# PowerPCB.net
KiCad netlist of a schematic drawn in EAGLE
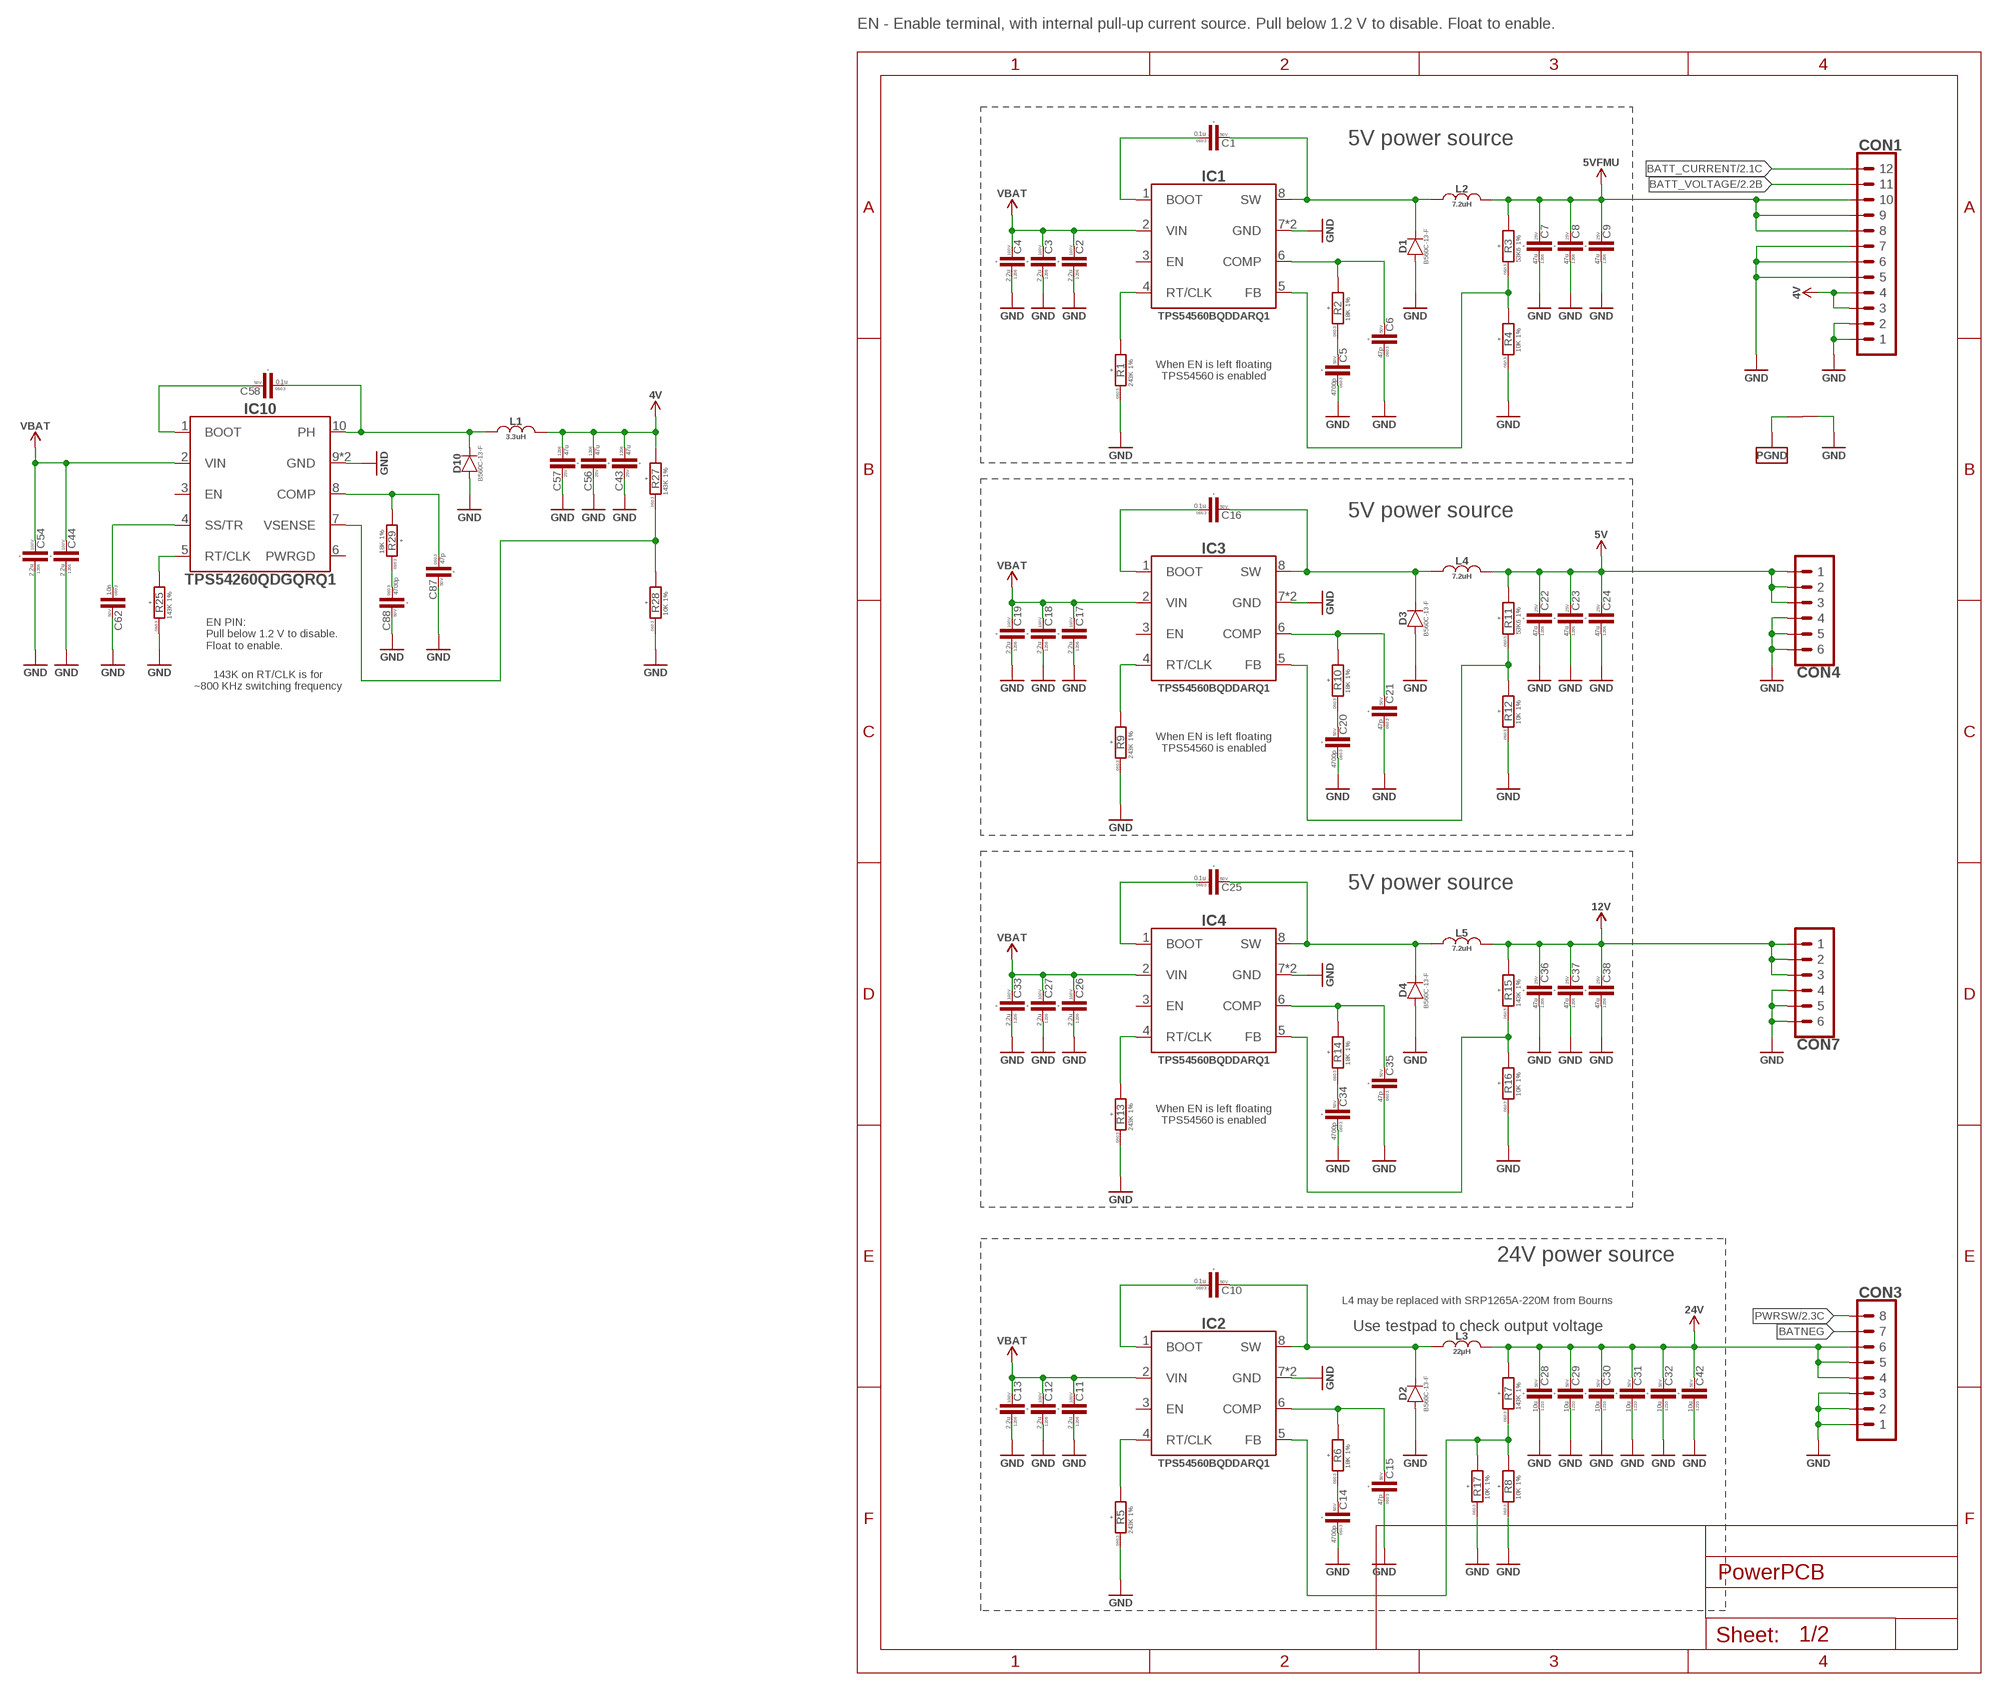
[diagram p0: schematic, sheet 1]
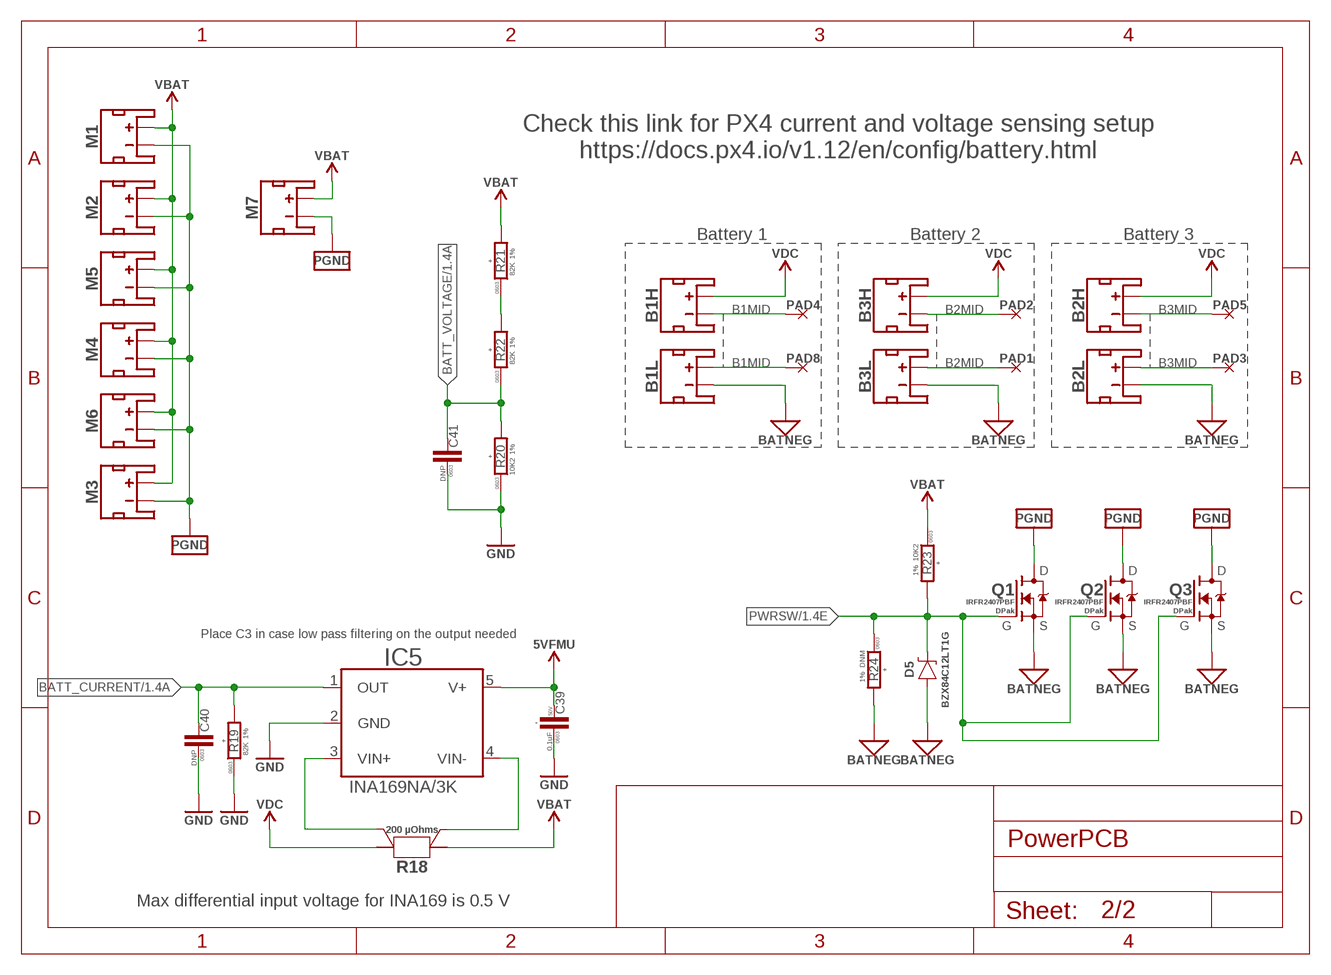
[diagram p1: schematic, sheet 2]

(export (version "E")
  (design (tool "Eeschema 10.0.6"))
  (components
    (comp (ref "C1")
      (value "0.1u")
      (footprint "eagle-import:C0603")
      (fields
        (field (name "PACKAGE") "0603")
        (field (name "ALLOCATED") "+")
        (field (name "LCSC#") "C14663")
        (field (name "MANF") "YAGEO")
        (field (name "MANF#") "CC0603KRX7R9BB104")
        (field (name "VOLTAGE") "50V")
      )
      (libsource (lib "eagle-import") (part "C-0603"))
    )
    (comp (ref "C2")
      (value "2.2u")
      (footprint "eagle-import:C1206")
      (fields
        (field (name "PACKAGE") "1206")
        (field (name "ALLOCATED") "+")
        (field (name "LCSC#") "C170101")
        (field (name "MANF") "Samsung Electro-Mechanics")
        (field (name "MANF#") "CL31B225KCHSNNE")
        (field (name "VOLTAGE") "100V")
      )
      (libsource (lib "eagle-import") (part "C-1206"))
    )
    (comp (ref "C3")
      (value "2.2u")
      (footprint "eagle-import:C1206")
      (fields
        (field (name "PACKAGE") "1206")
        (field (name "ALLOCATED") "+")
        (field (name "LCSC#") "C170101")
        (field (name "MANF") "Samsung Electro-Mechanics")
        (field (name "MANF#") "CL31B225KCHSNNE")
        (field (name "VOLTAGE") "100V")
      )
      (libsource (lib "eagle-import") (part "C-1206"))
    )
    (comp (ref "C4")
      (value "2.2u")
      (footprint "eagle-import:C1206")
      (fields
        (field (name "PACKAGE") "1206")
        (field (name "ALLOCATED") "+")
        (field (name "LCSC#") "C170101")
        (field (name "MANF") "Samsung Electro-Mechanics")
        (field (name "MANF#") "CL31B225KCHSNNE")
        (field (name "VOLTAGE") "100V")
      )
      (libsource (lib "eagle-import") (part "C-1206"))
    )
    (comp (ref "C5")
      (value "4700p")
      (footprint "eagle-import:C0603")
      (fields
        (field (name "PACKAGE") "0603")
        (field (name "ALLOCATED") "+")
        (field (name "LCSC#") "C106218")
        (field (name "MANF") "YAGEO")
        (field (name "MANF#") "CC0603KRX7R9BB472")
        (field (name "VOLTAGE") "50V")
      )
      (libsource (lib "eagle-import") (part "C-0603"))
    )
    (comp (ref "C6")
      (value "47p")
      (footprint "eagle-import:C0603")
      (fields
        (field (name "PACKAGE") "0603")
        (field (name "ALLOCATED") "+")
        (field (name "LCSC#") "C1671")
        (field (name "MANF") "Samsung Electro-Mechanics")
        (field (name "MANF#") "CL10C470JB8NNNC")
        (field (name "VOLTAGE") "50V")
      )
      (libsource (lib "eagle-import") (part "C-0603"))
    )
    (comp (ref "C7")
      (value "47u")
      (footprint "eagle-import:C1206")
      (fields
        (field (name "PACKAGE") "1206")
        (field (name "ALLOCATED") "+")
        (field (name "LCSC#") "C403725")
        (field (name "MANF") "Murata Electronics")
        (field (name "MANF#") "GRM31CR61E476ME44L")
        (field (name "VOLTAGE") "25V")
      )
      (libsource (lib "eagle-import") (part "C-1206"))
    )
    (comp (ref "C8")
      (value "47u")
      (footprint "eagle-import:C1206")
      (fields
        (field (name "PACKAGE") "1206")
        (field (name "ALLOCATED") "+")
        (field (name "LCSC#") "C403725")
        (field (name "MANF") "Murata Electronics")
        (field (name "MANF#") "GRM31CR61E476ME44L")
        (field (name "VOLTAGE") "25V")
      )
      (libsource (lib "eagle-import") (part "C-1206"))
    )
    (comp (ref "C9")
      (value "47u")
      (footprint "eagle-import:C1206")
      (fields
        (field (name "PACKAGE") "1206")
        (field (name "ALLOCATED") "+")
        (field (name "LCSC#") "C403725")
        (field (name "MANF") "Murata Electronics")
        (field (name "MANF#") "GRM31CR61E476ME44L")
        (field (name "VOLTAGE") "25V")
      )
      (libsource (lib "eagle-import") (part "C-1206"))
    )
    (comp (ref "C10")
      (value "0.1u")
      (footprint "eagle-import:C0603")
      (fields
        (field (name "PACKAGE") "0603")
        (field (name "ALLOCATED") "+")
        (field (name "LCSC#") "C14663")
        (field (name "MANF") "YAGEO")
        (field (name "MANF#") "CC0603KRX7R9BB104")
        (field (name "VOLTAGE") "50V")
      )
      (libsource (lib "eagle-import") (part "C-0603"))
    )
    (comp (ref "C11")
      (value "2.2u")
      (footprint "eagle-import:C1206")
      (fields
        (field (name "PACKAGE") "1206")
        (field (name "ALLOCATED") "+")
        (field (name "LCSC#") "C170101")
        (field (name "MANF") "Samsung Electro-Mechanics")
        (field (name "MANF#") "CL31B225KCHSNNE")
        (field (name "VOLTAGE") "100V")
      )
      (libsource (lib "eagle-import") (part "C-1206"))
    )
    (comp (ref "C12")
      (value "2.2u")
      (footprint "eagle-import:C1206")
      (fields
        (field (name "PACKAGE") "1206")
        (field (name "ALLOCATED") "+")
        (field (name "LCSC#") "C170101")
        (field (name "MANF") "Samsung Electro-Mechanics")
        (field (name "MANF#") "CL31B225KCHSNNE")
        (field (name "VOLTAGE") "100V")
      )
      (libsource (lib "eagle-import") (part "C-1206"))
    )
    (comp (ref "C13")
      (value "2.2u")
      (footprint "eagle-import:C1206")
      (fields
        (field (name "PACKAGE") "1206")
        (field (name "ALLOCATED") "+")
        (field (name "LCSC#") "C170101")
        (field (name "MANF") "Samsung Electro-Mechanics")
        (field (name "MANF#") "CL31B225KCHSNNE")
        (field (name "VOLTAGE") "100V")
      )
      (libsource (lib "eagle-import") (part "C-1206"))
    )
    (comp (ref "C14")
      (value "4700p")
      (footprint "eagle-import:C0603")
      (fields
        (field (name "PACKAGE") "0603")
        (field (name "ALLOCATED") "+")
        (field (name "LCSC#") "C106218")
        (field (name "MANF") "YAGEO")
        (field (name "MANF#") "CC0603KRX7R9BB472")
        (field (name "VOLTAGE") "50V")
      )
      (libsource (lib "eagle-import") (part "C-0603"))
    )
    (comp (ref "C15")
      (value "47p")
      (footprint "eagle-import:C0603")
      (fields
        (field (name "PACKAGE") "0603")
        (field (name "ALLOCATED") "+")
        (field (name "LCSC#") "C1671")
        (field (name "MANF") "Samsung Electro-Mechanics")
        (field (name "MANF#") "CL10C470JB8NNNC")
        (field (name "VOLTAGE") "50V")
      )
      (libsource (lib "eagle-import") (part "C-0603"))
    )
    (comp (ref "C16")
      (value "0.1u")
      (footprint "eagle-import:C0603")
      (fields
        (field (name "PACKAGE") "0603")
        (field (name "ALLOCATED") "+")
        (field (name "LCSC#") "C14663")
        (field (name "MANF") "YAGEO")
        (field (name "MANF#") "CC0603KRX7R9BB104")
        (field (name "VOLTAGE") "50V")
      )
      (libsource (lib "eagle-import") (part "C-0603"))
    )
    (comp (ref "C17")
      (value "2.2u")
      (footprint "eagle-import:C1206")
      (fields
        (field (name "PACKAGE") "1206")
        (field (name "ALLOCATED") "+")
        (field (name "LCSC#") "C170101")
        (field (name "MANF") "Samsung Electro-Mechanics")
        (field (name "MANF#") "CL31B225KCHSNNE")
        (field (name "VOLTAGE") "100V")
      )
      (libsource (lib "eagle-import") (part "C-1206"))
    )
    (comp (ref "C18")
      (value "2.2u")
      (footprint "eagle-import:C1206")
      (fields
        (field (name "PACKAGE") "1206")
        (field (name "ALLOCATED") "+")
        (field (name "LCSC#") "C170101")
        (field (name "MANF") "Samsung Electro-Mechanics")
        (field (name "MANF#") "CL31B225KCHSNNE")
        (field (name "VOLTAGE") "100V")
      )
      (libsource (lib "eagle-import") (part "C-1206"))
    )
    (comp (ref "C19")
      (value "2.2u")
      (footprint "eagle-import:C1206")
      (fields
        (field (name "PACKAGE") "1206")
        (field (name "ALLOCATED") "+")
        (field (name "LCSC#") "C170101")
        (field (name "MANF") "Samsung Electro-Mechanics")
        (field (name "MANF#") "CL31B225KCHSNNE")
        (field (name "VOLTAGE") "100V")
      )
      (libsource (lib "eagle-import") (part "C-1206"))
    )
    (comp (ref "C20")
      (value "4700p")
      (footprint "eagle-import:C0603")
      (fields
        (field (name "PACKAGE") "0603")
        (field (name "ALLOCATED") "+")
        (field (name "LCSC#") "C106218")
        (field (name "MANF") "YAGEO")
        (field (name "MANF#") "CC0603KRX7R9BB472")
        (field (name "VOLTAGE") "50V")
      )
      (libsource (lib "eagle-import") (part "C-0603"))
    )
    (comp (ref "C21")
      (value "47p")
      (footprint "eagle-import:C0603")
      (fields
        (field (name "PACKAGE") "0603")
        (field (name "ALLOCATED") "+")
        (field (name "LCSC#") "C1671")
        (field (name "MANF") "Samsung Electro-Mechanics")
        (field (name "MANF#") "CL10C470JB8NNNC")
        (field (name "VOLTAGE") "50V")
      )
      (libsource (lib "eagle-import") (part "C-0603"))
    )
    (comp (ref "C22")
      (value "47u")
      (footprint "eagle-import:C1206")
      (fields
        (field (name "PACKAGE") "1206")
        (field (name "ALLOCATED") "+")
        (field (name "LCSC#") "C403725")
        (field (name "MANF") "Murata Electronics")
        (field (name "MANF#") "GRM31CR61E476ME44L")
        (field (name "VOLTAGE") "25V")
      )
      (libsource (lib "eagle-import") (part "C-1206"))
    )
    (comp (ref "C23")
      (value "47u")
      (footprint "eagle-import:C1206")
      (fields
        (field (name "PACKAGE") "1206")
        (field (name "ALLOCATED") "+")
        (field (name "LCSC#") "C403725")
        (field (name "MANF") "Murata Electronics")
        (field (name "MANF#") "GRM31CR61E476ME44L")
        (field (name "VOLTAGE") "25V")
      )
      (libsource (lib "eagle-import") (part "C-1206"))
    )
    (comp (ref "C24")
      (value "47u")
      (footprint "eagle-import:C1206")
      (fields
        (field (name "PACKAGE") "1206")
        (field (name "ALLOCATED") "+")
        (field (name "LCSC#") "C403725")
        (field (name "MANF") "Murata Electronics")
        (field (name "MANF#") "GRM31CR61E476ME44L")
        (field (name "VOLTAGE") "25V")
      )
      (libsource (lib "eagle-import") (part "C-1206"))
    )
    (comp (ref "C25")
      (value "0.1u")
      (footprint "eagle-import:C0603")
      (fields
        (field (name "PACKAGE") "0603")
        (field (name "ALLOCATED") "+")
        (field (name "LCSC#") "C14663")
        (field (name "MANF") "YAGEO")
        (field (name "MANF#") "CC0603KRX7R9BB104")
        (field (name "VOLTAGE") "50V")
      )
      (libsource (lib "eagle-import") (part "C-0603"))
    )
    (comp (ref "C26")
      (value "2.2u")
      (footprint "eagle-import:C1206")
      (fields
        (field (name "PACKAGE") "1206")
        (field (name "ALLOCATED") "+")
        (field (name "LCSC#") "C170101")
        (field (name "MANF") "Samsung Electro-Mechanics")
        (field (name "MANF#") "CL31B225KCHSNNE")
        (field (name "VOLTAGE") "100V")
      )
      (libsource (lib "eagle-import") (part "C-1206"))
    )
    (comp (ref "C27")
      (value "2.2u")
      (footprint "eagle-import:C1206")
      (fields
        (field (name "PACKAGE") "1206")
        (field (name "ALLOCATED") "+")
        (field (name "LCSC#") "C170101")
        (field (name "MANF") "Samsung Electro-Mechanics")
        (field (name "MANF#") "CL31B225KCHSNNE")
        (field (name "VOLTAGE") "100V")
      )
      (libsource (lib "eagle-import") (part "C-1206"))
    )
    (comp (ref "C28")
      (value "10u")
      (footprint "eagle-import:C1210")
      (fields
        (field (name "PACKAGE") "1210")
        (field (name "ALLOCATED") "+")
        (field (name "LCSC#") "C77102")
        (field (name "MANF") "Murata Electronics")
        (field (name "MANF#") "GRM32ER71H106K")
        (field (name "VOLTAGE") "50V")
      )
      (libsource (lib "eagle-import") (part "C-1210"))
    )
    (comp (ref "C29")
      (value "10u")
      (footprint "eagle-import:C1210")
      (fields
        (field (name "PACKAGE") "1210")
        (field (name "ALLOCATED") "+")
        (field (name "LCSC#") "C77102")
        (field (name "MANF") "Murata Electronics")
        (field (name "MANF#") "GRM32ER71H106K")
        (field (name "VOLTAGE") "50V")
      )
      (libsource (lib "eagle-import") (part "C-1210"))
    )
    (comp (ref "C30")
      (value "10u")
      (footprint "eagle-import:C1210")
      (fields
        (field (name "PACKAGE") "1210")
        (field (name "ALLOCATED") "+")
        (field (name "LCSC#") "C77102")
        (field (name "MANF") "Murata Electronics")
        (field (name "MANF#") "GRM32ER71H106K")
        (field (name "VOLTAGE") "50V")
      )
      (libsource (lib "eagle-import") (part "C-1210"))
    )
    (comp (ref "C31")
      (value "10u")
      (footprint "eagle-import:C1210")
      (fields
        (field (name "PACKAGE") "1210")
        (field (name "ALLOCATED") "+")
        (field (name "LCSC#") "C77102")
        (field (name "MANF") "Murata Electronics")
        (field (name "MANF#") "GRM32ER71H106K")
        (field (name "VOLTAGE") "50V")
      )
      (libsource (lib "eagle-import") (part "C-1210"))
    )
    (comp (ref "C32")
      (value "10u")
      (footprint "eagle-import:C1210")
      (fields
        (field (name "PACKAGE") "1210")
        (field (name "ALLOCATED") "+")
        (field (name "LCSC#") "C77102")
        (field (name "MANF") "Murata Electronics")
        (field (name "MANF#") "GRM32ER71H106K")
        (field (name "VOLTAGE") "50V")
      )
      (libsource (lib "eagle-import") (part "C-1210"))
    )
    (comp (ref "C33")
      (value "2.2u")
      (footprint "eagle-import:C1206")
      (fields
        (field (name "PACKAGE") "1206")
        (field (name "ALLOCATED") "+")
        (field (name "LCSC#") "C170101")
        (field (name "MANF") "Samsung Electro-Mechanics")
        (field (name "MANF#") "CL31B225KCHSNNE")
        (field (name "VOLTAGE") "100V")
      )
      (libsource (lib "eagle-import") (part "C-1206"))
    )
    (comp (ref "C34")
      (value "4700p")
      (footprint "eagle-import:C0603")
      (fields
        (field (name "PACKAGE") "0603")
        (field (name "ALLOCATED") "+")
        (field (name "LCSC#") "C106218")
        (field (name "MANF") "YAGEO")
        (field (name "MANF#") "CC0603KRX7R9BB472")
        (field (name "VOLTAGE") "50V")
      )
      (libsource (lib "eagle-import") (part "C-0603"))
    )
    (comp (ref "C35")
      (value "47p")
      (footprint "eagle-import:C0603")
      (fields
        (field (name "PACKAGE") "0603")
        (field (name "ALLOCATED") "+")
        (field (name "LCSC#") "C1671")
        (field (name "MANF") "Samsung Electro-Mechanics")
        (field (name "MANF#") "CL10C470JB8NNNC")
        (field (name "VOLTAGE") "50V")
      )
      (libsource (lib "eagle-import") (part "C-0603"))
    )
    (comp (ref "C36")
      (value "47u")
      (footprint "eagle-import:C1206")
      (fields
        (field (name "PACKAGE") "1206")
        (field (name "ALLOCATED") "+")
        (field (name "LCSC#") "C403725")
        (field (name "MANF") "Murata Electronics")
        (field (name "MANF#") "GRM31CR61E476ME44L")
        (field (name "VOLTAGE") "25V")
      )
      (libsource (lib "eagle-import") (part "C-1206"))
    )
    (comp (ref "C37")
      (value "47u")
      (footprint "eagle-import:C1206")
      (fields
        (field (name "PACKAGE") "1206")
        (field (name "ALLOCATED") "+")
        (field (name "LCSC#") "C403725")
        (field (name "MANF") "Murata Electronics")
        (field (name "MANF#") "GRM31CR61E476ME44L")
        (field (name "VOLTAGE") "25V")
      )
      (libsource (lib "eagle-import") (part "C-1206"))
    )
    (comp (ref "C38")
      (value "47u")
      (footprint "eagle-import:C1206")
      (fields
        (field (name "PACKAGE") "1206")
        (field (name "ALLOCATED") "+")
        (field (name "LCSC#") "C403725")
        (field (name "MANF") "Murata Electronics")
        (field (name "MANF#") "GRM31CR61E476ME44L")
        (field (name "VOLTAGE") "25V")
      )
      (libsource (lib "eagle-import") (part "C-1206"))
    )
    (comp (ref "C42")
      (value "10u")
      (footprint "eagle-import:C1210")
      (fields
        (field (name "PACKAGE") "1210")
        (field (name "ALLOCATED") "+")
        (field (name "LCSC#") "C77102")
        (field (name "MANF") "Murata Electronics")
        (field (name "MANF#") "GRM32ER71H106K")
        (field (name "VOLTAGE") "50V")
      )
      (libsource (lib "eagle-import") (part "C-1210"))
    )
    (comp (ref "C43")
      (value "47u")
      (footprint "eagle-import:C1206")
      (fields
        (field (name "PACKAGE") "1206")
        (field (name "ALLOCATED") "+")
        (field (name "LCSC#") "C403725")
        (field (name "MANF") "Murata Electronics")
        (field (name "MANF#") "GRM31CR61E476ME44L")
        (field (name "VOLTAGE") "25V")
      )
      (libsource (lib "eagle-import") (part "C-1206"))
    )
    (comp (ref "C44")
      (value "2.2u")
      (footprint "eagle-import:C1206")
      (fields
        (field (name "PACKAGE") "1206")
        (field (name "ALLOCATED") "+")
        (field (name "LCSC#") "C170101")
        (field (name "MANF") "Samsung Electro-Mechanics")
        (field (name "MANF#") "CL31B225KCHSNNE")
        (field (name "VOLTAGE") "100V")
      )
      (libsource (lib "eagle-import") (part "C-1206"))
    )
    (comp (ref "C54")
      (value "2.2u")
      (footprint "eagle-import:C1206")
      (fields
        (field (name "PACKAGE") "1206")
        (field (name "ALLOCATED") "+")
        (field (name "LCSC#") "C170101")
        (field (name "MANF") "Samsung Electro-Mechanics")
        (field (name "MANF#") "CL31B225KCHSNNE")
        (field (name "VOLTAGE") "100V")
      )
      (libsource (lib "eagle-import") (part "C-1206"))
    )
    (comp (ref "C56")
      (value "47u")
      (footprint "eagle-import:C1206")
      (fields
        (field (name "PACKAGE") "1206")
        (field (name "ALLOCATED") "+")
        (field (name "LCSC#") "C403725")
        (field (name "MANF") "Murata Electronics")
        (field (name "MANF#") "GRM31CR61E476ME44L")
        (field (name "VOLTAGE") "25V")
      )
      (libsource (lib "eagle-import") (part "C-1206"))
    )
    (comp (ref "C57")
      (value "47u")
      (footprint "eagle-import:C1206")
      (fields
        (field (name "PACKAGE") "1206")
        (field (name "ALLOCATED") "+")
        (field (name "LCSC#") "C403725")
        (field (name "MANF") "Murata Electronics")
        (field (name "MANF#") "GRM31CR61E476ME44L")
        (field (name "VOLTAGE") "25V")
      )
      (libsource (lib "eagle-import") (part "C-1206"))
    )
    (comp (ref "C58")
      (value "0.1u")
      (footprint "eagle-import:C0603")
      (fields
        (field (name "PACKAGE") "0603")
        (field (name "ALLOCATED") "+")
        (field (name "LCSC#") "C14663")
        (field (name "MANF") "YAGEO")
        (field (name "MANF#") "CC0603KRX7R9BB104")
        (field (name "VOLTAGE") "50V")
      )
      (libsource (lib "eagle-import") (part "C-0603"))
    )
    (comp (ref "C62")
      (value "10n")
      (footprint "eagle-import:C0603")
      (fields (field (name "PACKAGE") "0603") (field (name "VOLTAGE") "50V"))
      (libsource (lib "eagle-import") (part "C-0603"))
    )
    (comp (ref "C87")
      (value "47p")
      (footprint "eagle-import:C0603")
      (fields
        (field (name "PACKAGE") "0603")
        (field (name "ALLOCATED") "+")
        (field (name "LCSC#") "C1671")
        (field (name "MANF") "Samsung Electro-Mechanics")
        (field (name "MANF#") "CL10C470JB8NNNC")
        (field (name "VOLTAGE") "50V")
      )
      (libsource (lib "eagle-import") (part "C-0603"))
    )
    (comp (ref "C88")
      (value "4700p")
      (footprint "eagle-import:C0603")
      (fields
        (field (name "PACKAGE") "0603")
        (field (name "ALLOCATED") "+")
        (field (name "LCSC#") "C106218")
        (field (name "MANF") "YAGEO")
        (field (name "MANF#") "CC0603KRX7R9BB472")
        (field (name "VOLTAGE") "50V")
      )
      (libsource (lib "eagle-import") (part "C-0603"))
    )
    (comp (ref "CON1")
      (value "PINHEAD_1X12-2.54-FEMALE")
      (footprint "eagle-import:1X12-PTH-2.54-FEMALE")
      (libsource (lib "eagle-import") (part "PINHEAD_1X12-2.54-FEMALE"))
    )
    (comp (ref "CON3")
      (value "PINHEAD_1X08-2.54-FEMALE")
      (footprint "eagle-import:1X08-PTH-2.54-FEMALE")
      (libsource (lib "eagle-import") (part "PINHEAD_1X08-2.54-FEMALE"))
    )
    (comp (ref "CON4")
      (value "PINHEAD_1X06-2.54-FEMALE")
      (footprint "eagle-import:1X06-PTH-2.54-FEMALE")
      (libsource (lib "eagle-import") (part "PINHEAD_1X06-2.54-FEMALE"))
    )
    (comp (ref "CON7")
      (value "PINHEAD_1X06-2.54-FEMALE")
      (footprint "eagle-import:1X06-PTH-2.54-FEMALE")
      (libsource (lib "eagle-import") (part "PINHEAD_1X06-2.54-FEMALE"))
    )
    (comp (ref "D1")
      (value "B560C")
      (footprint "eagle-import:DO-214AB(SMC)")
      (fields (field (name "MANF#") "B560C-13-F") (field (name "MANF") "Diodes Incorporated"))
      (libsource (lib "eagle-import") (part "B560C"))
    )
    (comp (ref "D2")
      (value "B560C")
      (footprint "eagle-import:DO-214AB(SMC)")
      (fields (field (name "MANF#") "B560C-13-F") (field (name "MANF") "Diodes Incorporated"))
      (libsource (lib "eagle-import") (part "B560C"))
    )
    (comp (ref "D3")
      (value "B560C")
      (footprint "eagle-import:DO-214AB(SMC)")
      (fields (field (name "MANF#") "B560C-13-F") (field (name "MANF") "Diodes Incorporated"))
      (libsource (lib "eagle-import") (part "B560C"))
    )
    (comp (ref "D4")
      (value "B560C")
      (footprint "eagle-import:DO-214AB(SMC)")
      (fields (field (name "MANF#") "B560C-13-F") (field (name "MANF") "Diodes Incorporated"))
      (libsource (lib "eagle-import") (part "B560C"))
    )
    (comp (ref "D10")
      (value "B560C")
      (footprint "eagle-import:DO-214AB(SMC)")
      (fields (field (name "MANF#") "B560C-13-F") (field (name "MANF") "Diodes Incorporated"))
      (libsource (lib "eagle-import") (part "B560C"))
    )
    (comp (ref "IC1")
      (value "TPS54560B")
      (footprint "eagle-import:SOIC8-POWERPAD")
      (fields (field (name "MANF#") "TPS54560BQDDARQ1") (field (name "MANF") "Texas Instruments"))
      (libsource (lib "eagle-import") (part "TPS54560B"))
    )
    (comp (ref "IC2")
      (value "TPS54560B")
      (footprint "eagle-import:SOIC8-POWERPAD")
      (fields (field (name "MANF#") "TPS54560BQDDARQ1") (field (name "MANF") "Texas Instruments"))
      (libsource (lib "eagle-import") (part "TPS54560B"))
    )
    (comp (ref "IC3")
      (value "TPS54560B")
      (footprint "eagle-import:SOIC8-POWERPAD")
      (fields (field (name "MANF#") "TPS54560BQDDARQ1") (field (name "MANF") "Texas Instruments"))
      (libsource (lib "eagle-import") (part "TPS54560B"))
    )
    (comp (ref "IC4")
      (value "TPS54560B")
      (footprint "eagle-import:SOIC8-POWERPAD")
      (fields (field (name "MANF#") "TPS54560BQDDARQ1") (field (name "MANF") "Texas Instruments"))
      (libsource (lib "eagle-import") (part "TPS54560B"))
    )
    (comp (ref "IC10")
      (value "TPS54260")
      (footprint "eagle-import:MSOP10")
      (fields
        (field (name "MANF#") "TPS54260DGQR")
        (field (name "MANF") "Texas Instruments")
        (field (name "DIGIKEY#") "296-28183-1-ND")
        (field (name "MANF_1") "Texas Instruments")
        (field (name "MANF#_1") "TPS54260QDGQRQ1")
      )
      (libsource (lib "eagle-import") (part "TPS54260"))
    )
    (comp (ref "J1")
      (value "CONNECTION-7MM")
      (footprint "eagle-import:CONNECTION_7MM")
      (libsource (lib "eagle-import") (part "CONNECTION-7MM"))
    )
    (comp (ref "L1")
      (value "3.3uH")
      (footprint "eagle-import:IHLP-2020BZ-01")
      (fields (field (name "MANF") "Vishay Precision Group"))
      (libsource (lib "eagle-import") (part "3.3µH-IHLP-202BZ"))
    )
    (comp (ref "L2")
      (value "7.2uH")
      (footprint "eagle-import:1064")
      (fields (field (name "MANF") "Wurth Elektronik"))
      (libsource (lib "eagle-import") (part "7.2µH-1064"))
    )
    (comp (ref "L3")
      (value "22µH")
      (footprint "eagle-import:SRP1265A")
      (fields (field (name "MANF") "Bourns"))
      (libsource (lib "eagle-import") (part "22µH-SRP1265A"))
    )
    (comp (ref "L4")
      (value "7.2uH")
      (footprint "eagle-import:1064")
      (fields (field (name "MANF") "Wurth Elektronik"))
      (libsource (lib "eagle-import") (part "7.2µH-1064"))
    )
    (comp (ref "L5")
      (value "7.2uH")
      (footprint "eagle-import:1064")
      (fields (field (name "MANF") "Wurth Elektronik"))
      (libsource (lib "eagle-import") (part "7.2µH-1064"))
    )
    (comp (ref "R1")
      (value "243K")
      (footprint "eagle-import:R0603")
      (fields
        (field (name "PACKAGE") "0603")
        (field (name "TOLERANCE") "1%")
        (field (name "ALLOCATED") "+")
        (field (name "LCSC#") "C23351")
        (field (name "MANF") "UNI-ROYAL(Uniroyal Elec)")
        (field (name "MANF#") "0603WAF2433T5E")
      )
      (libsource (lib "eagle-import") (part "R-0603-1%"))
    )
    (comp (ref "R2")
      (value "18K")
      (footprint "eagle-import:R0603")
      (fields
        (field (name "PACKAGE") "0603")
        (field (name "TOLERANCE") "1%")
        (field (name "ALLOCATED") "+")
        (field (name "LCSC#") "C25810")
        (field (name "MANF") "UNI-ROYAL")
        (field (name "MANF#") "0603WAF1802T5E")
      )
      (libsource (lib "eagle-import") (part "R-0603-1%"))
    )
    (comp (ref "R3")
      (value "53K6")
      (footprint "eagle-import:R0603")
      (fields
        (field (name "PACKAGE") "0603")
        (field (name "TOLERANCE") "1%")
        (field (name "ALLOCATED") "+")
        (field (name "LCSC#") "C23074")
        (field (name "MANF") "UNI-ROYAL(Uniroyal Elec)")
        (field (name "MANF#") "0603WAF5362T5E")
      )
      (libsource (lib "eagle-import") (part "R-0603-1%"))
    )
    (comp (ref "R4")
      (value "10K")
      (footprint "eagle-import:R0603")
      (fields
        (field (name "PACKAGE") "0603")
        (field (name "TOLERANCE") "1%")
        (field (name "ALLOCATED") "+")
        (field (name "LCSC#") "C160601")
        (field (name "MANF") "YAGEO")
        (field (name "MANF#") "RT0603FRD0710KL")
      )
      (libsource (lib "eagle-import") (part "R-0603-1%"))
    )
    (comp (ref "R5")
      (value "243K")
      (footprint "eagle-import:R0603")
      (fields
        (field (name "PACKAGE") "0603")
        (field (name "TOLERANCE") "1%")
        (field (name "ALLOCATED") "+")
        (field (name "LCSC#") "C23351")
        (field (name "MANF") "UNI-ROYAL(Uniroyal Elec)")
        (field (name "MANF#") "0603WAF2433T5E")
      )
      (libsource (lib "eagle-import") (part "R-0603-1%"))
    )
    (comp (ref "R6")
      (value "18K")
      (footprint "eagle-import:R0603")
      (fields
        (field (name "PACKAGE") "0603")
        (field (name "TOLERANCE") "1%")
        (field (name "ALLOCATED") "+")
        (field (name "LCSC#") "C25810")
        (field (name "MANF") "UNI-ROYAL")
        (field (name "MANF#") "0603WAF1802T5E")
      )
      (libsource (lib "eagle-import") (part "R-0603-1%"))
    )
    (comp (ref "R7")
      (value "143K")
      (footprint "eagle-import:R0603")
      (fields
        (field (name "PACKAGE") "0603")
        (field (name "TOLERANCE") "1%")
        (field (name "ALLOCATED") "+")
        (field (name "LCSC#") "C22877")
        (field (name "MANF") "UNI-ROYAL(Uniroyal Elec)")
        (field (name "MANF#") "0603WAF1433T5E")
      )
      (libsource (lib "eagle-import") (part "R-0603-1%"))
    )
    (comp (ref "R8")
      (value "10K")
      (footprint "eagle-import:R0603")
      (fields
        (field (name "PACKAGE") "0603")
        (field (name "TOLERANCE") "1%")
        (field (name "ALLOCATED") "+")
        (field (name "LCSC#") "C160601")
        (field (name "MANF") "YAGEO")
        (field (name "MANF#") "RT0603FRD0710KL")
      )
      (libsource (lib "eagle-import") (part "R-0603-1%"))
    )
    (comp (ref "R9")
      (value "243K")
      (footprint "eagle-import:R0603")
      (fields
        (field (name "PACKAGE") "0603")
        (field (name "TOLERANCE") "1%")
        (field (name "ALLOCATED") "+")
        (field (name "LCSC#") "C23351")
        (field (name "MANF") "UNI-ROYAL(Uniroyal Elec)")
        (field (name "MANF#") "0603WAF2433T5E")
      )
      (libsource (lib "eagle-import") (part "R-0603-1%"))
    )
    (comp (ref "R10")
      (value "18K")
      (footprint "eagle-import:R0603")
      (fields
        (field (name "PACKAGE") "0603")
        (field (name "TOLERANCE") "1%")
        (field (name "ALLOCATED") "+")
        (field (name "LCSC#") "C25810")
        (field (name "MANF") "UNI-ROYAL")
        (field (name "MANF#") "0603WAF1802T5E")
      )
      (libsource (lib "eagle-import") (part "R-0603-1%"))
    )
    (comp (ref "R11")
      (value "53K6")
      (footprint "eagle-import:R0603")
      (fields
        (field (name "PACKAGE") "0603")
        (field (name "TOLERANCE") "1%")
        (field (name "ALLOCATED") "+")
        (field (name "LCSC#") "C23074")
        (field (name "MANF") "UNI-ROYAL(Uniroyal Elec)")
        (field (name "MANF#") "0603WAF5362T5E")
      )
      (libsource (lib "eagle-import") (part "R-0603-1%"))
    )
    (comp (ref "R12")
      (value "10K")
      (footprint "eagle-import:R0603")
      (fields
        (field (name "PACKAGE") "0603")
        (field (name "TOLERANCE") "1%")
        (field (name "ALLOCATED") "+")
        (field (name "LCSC#") "C160601")
        (field (name "MANF") "YAGEO")
        (field (name "MANF#") "RT0603FRD0710KL")
      )
      (libsource (lib "eagle-import") (part "R-0603-1%"))
    )
    (comp (ref "R13")
      (value "243K")
      (footprint "eagle-import:R0603")
      (fields
        (field (name "PACKAGE") "0603")
        (field (name "TOLERANCE") "1%")
        (field (name "ALLOCATED") "+")
        (field (name "LCSC#") "C23351")
        (field (name "MANF") "UNI-ROYAL(Uniroyal Elec)")
        (field (name "MANF#") "0603WAF2433T5E")
      )
      (libsource (lib "eagle-import") (part "R-0603-1%"))
    )
    (comp (ref "R14")
      (value "18K")
      (footprint "eagle-import:R0603")
      (fields
        (field (name "PACKAGE") "0603")
        (field (name "TOLERANCE") "1%")
        (field (name "ALLOCATED") "+")
        (field (name "LCSC#") "C25810")
        (field (name "MANF") "UNI-ROYAL")
        (field (name "MANF#") "0603WAF1802T5E")
      )
      (libsource (lib "eagle-import") (part "R-0603-1%"))
    )
    (comp (ref "R15")
      (value "143K")
      (footprint "eagle-import:R0603")
      (fields
        (field (name "PACKAGE") "0603")
        (field (name "TOLERANCE") "1%")
        (field (name "ALLOCATED") "+")
        (field (name "LCSC#") "C23074")
        (field (name "MANF") "UNI-ROYAL(Uniroyal Elec)")
        (field (name "MANF#") "0603WAF5362T5E")
      )
      (libsource (lib "eagle-import") (part "R-0603-1%"))
    )
    (comp (ref "R16")
      (value "10K")
      (footprint "eagle-import:R0603")
      (fields
        (field (name "PACKAGE") "0603")
        (field (name "TOLERANCE") "1%")
        (field (name "ALLOCATED") "+")
        (field (name "LCSC#") "C160601")
        (field (name "MANF") "YAGEO")
        (field (name "MANF#") "RT0603FRD0710KL")
      )
      (libsource (lib "eagle-import") (part "R-0603-1%"))
    )
    (comp (ref "R17")
      (value "10K")
      (footprint "eagle-import:R0603")
      (fields
        (field (name "PACKAGE") "0603")
        (field (name "TOLERANCE") "1%")
        (field (name "ALLOCATED") "+")
        (field (name "LCSC#") "C160601")
        (field (name "MANF") "YAGEO")
        (field (name "MANF#") "RT0603FRD0710KL")
      )
      (libsource (lib "eagle-import") (part "R-0603-1%"))
    )
    (comp (ref "R25")
      (value "143K")
      (footprint "eagle-import:R0603")
      (fields
        (field (name "PACKAGE") "0603")
        (field (name "TOLERANCE") "1%")
        (field (name "ALLOCATED") "+")
        (field (name "LCSC#") "C22877")
        (field (name "MANF") "UNI-ROYAL(Uniroyal Elec)")
        (field (name "MANF#") "0603WAF1433T5E")
      )
      (libsource (lib "eagle-import") (part "R-0603-1%"))
    )
    (comp (ref "R27")
      (value "143K")
      (footprint "eagle-import:R0603")
      (fields
        (field (name "PACKAGE") "0603")
        (field (name "TOLERANCE") "1%")
        (field (name "ALLOCATED") "+")
        (field (name "LCSC#") "C22877")
        (field (name "MANF") "UNI-ROYAL(Uniroyal Elec)")
        (field (name "MANF#") "0603WAF1433T5E")
      )
      (libsource (lib "eagle-import") (part "R-0603-1%"))
    )
    (comp (ref "R28")
      (value "10K")
      (footprint "eagle-import:R0603")
      (fields
        (field (name "PACKAGE") "0603")
        (field (name "TOLERANCE") "1%")
        (field (name "ALLOCATED") "+")
        (field (name "LCSC#") "C160601")
        (field (name "MANF") "YAGEO")
        (field (name "MANF#") "RT0603FRD0710KL")
      )
      (libsource (lib "eagle-import") (part "R-0603-1%"))
    )
    (comp (ref "R29")
      (value "18K")
      (footprint "eagle-import:R0603")
      (fields
        (field (name "PACKAGE") "0603")
        (field (name "TOLERANCE") "1%")
        (field (name "ALLOCATED") "+")
        (field (name "LCSC#") "C25810")
        (field (name "MANF") "UNI-ROYAL")
        (field (name "MANF#") "0603WAF1802T5E")
      )
      (libsource (lib "eagle-import") (part "R-0603-1%"))
    )
    (comp (ref "B1H")
      (value "BATTERY_CON-XT60PW-M")
      (footprint "eagle-import:XT60PW-M")
      (libsource (lib "eagle-import") (part "BATTERY_CON-XT60PW-M"))
    )
    (comp (ref "B1L")
      (value "BATTERY_CON-XT60PW-M")
      (footprint "eagle-import:XT60PW-M")
      (libsource (lib "eagle-import") (part "BATTERY_CON-XT60PW-M"))
    )
    (comp (ref "B2H")
      (value "BATTERY_CON-XT60PW-M")
      (footprint "eagle-import:XT60PW-M")
      (libsource (lib "eagle-import") (part "BATTERY_CON-XT60PW-M"))
    )
    (comp (ref "B2L")
      (value "BATTERY_CON-XT60PW-M")
      (footprint "eagle-import:XT60PW-M")
      (libsource (lib "eagle-import") (part "BATTERY_CON-XT60PW-M"))
    )
    (comp (ref "B3H")
      (value "BATTERY_CON-XT60PW-M")
      (footprint "eagle-import:XT60PW-M")
      (libsource (lib "eagle-import") (part "BATTERY_CON-XT60PW-M"))
    )
    (comp (ref "B3L")
      (value "BATTERY_CON-XT60PW-M")
      (footprint "eagle-import:XT60PW-M")
      (libsource (lib "eagle-import") (part "BATTERY_CON-XT60PW-M"))
    )
    (comp (ref "C39")
      (value "0.1uF")
      (footprint "eagle-import:C0603")
      (fields
        (field (name "PACKAGE") "0603")
        (field (name "ALLOCATED") "+")
        (field (name "LCSC#") "C14663")
        (field (name "MANF") "YAGEO")
        (field (name "MANF#") "CC0603KRX7R9BB104")
        (field (name "VOLTAGE") "50V")
      )
      (libsource (lib "eagle-import") (part "C-0603"))
    )
    (comp (ref "C40")
      (value "DNP")
      (footprint "eagle-import:C0603")
      (fields (field (name "PACKAGE") "0603"))
      (libsource (lib "eagle-import") (part "C-0603"))
    )
    (comp (ref "C41")
      (value "DNP")
      (footprint "eagle-import:C0603")
      (fields (field (name "PACKAGE") "0603"))
      (libsource (lib "eagle-import") (part "C-0603"))
    )
    (comp (ref "D5")
      (value "BZX84C12")
      (footprint "eagle-import:SOT23")
      (fields (field (name "MANF") "ON Semiconductor") (field (name "MANF#") "BZX84C12LT1G"))
      (libsource (lib "eagle-import") (part "BZX84C12"))
    )
    (comp (ref "IC5")
      (value "INA169")
      (footprint "eagle-import:SOT23-5")
      (fields (field (name "MANF") "Texas Instruments"))
      (libsource (lib "eagle-import") (part "INA169"))
    )
    (comp (ref "M1")
      (value "BATTERY_CON-XT30-RA")
      (footprint "eagle-import:XT30-RA")
      (fields (field (name "MANF") "AMASS"))
      (libsource (lib "eagle-import") (part "BATTERY_CON-XT30-RA"))
    )
    (comp (ref "M2")
      (value "BATTERY_CON-XT30-RA")
      (footprint "eagle-import:XT30-RA")
      (fields (field (name "MANF") "AMASS"))
      (libsource (lib "eagle-import") (part "BATTERY_CON-XT30-RA"))
    )
    (comp (ref "M3")
      (value "BATTERY_CON-XT30-RA")
      (footprint "eagle-import:XT30-RA")
      (fields (field (name "MANF") "AMASS"))
      (libsource (lib "eagle-import") (part "BATTERY_CON-XT30-RA"))
    )
    (comp (ref "M4")
      (value "BATTERY_CON-XT30-RA")
      (footprint "eagle-import:XT30-RA")
      (fields (field (name "MANF") "AMASS"))
      (libsource (lib "eagle-import") (part "BATTERY_CON-XT30-RA"))
    )
    (comp (ref "M5")
      (value "BATTERY_CON-XT30-RA")
      (footprint "eagle-import:XT30-RA")
      (fields (field (name "MANF") "AMASS"))
      (libsource (lib "eagle-import") (part "BATTERY_CON-XT30-RA"))
    )
    (comp (ref "M6")
      (value "BATTERY_CON-XT30-RA")
      (footprint "eagle-import:XT30-RA")
      (fields (field (name "MANF") "AMASS"))
      (libsource (lib "eagle-import") (part "BATTERY_CON-XT30-RA"))
    )
    (comp (ref "M7")
      (value "BATTERY_CON-XT30-RA")
      (footprint "eagle-import:XT30-RA")
      (fields (field (name "MANF") "AMASS"))
      (libsource (lib "eagle-import") (part "BATTERY_CON-XT30-RA"))
    )
    (comp (ref "PAD1")
      (value "PAD-10X4")
      (footprint "eagle-import:10X4")
      (libsource (lib "eagle-import") (part "PAD-10X4"))
    )
    (comp (ref "PAD2")
      (value "PAD-10X4")
      (footprint "eagle-import:10X4")
      (libsource (lib "eagle-import") (part "PAD-10X4"))
    )
    (comp (ref "PAD3")
      (value "PAD-10X4")
      (footprint "eagle-import:10X4")
      (libsource (lib "eagle-import") (part "PAD-10X4"))
    )
    (comp (ref "PAD4")
      (value "PAD-10X4")
      (footprint "eagle-import:10X4")
      (libsource (lib "eagle-import") (part "PAD-10X4"))
    )
    (comp (ref "PAD5")
      (value "PAD-10X4")
      (footprint "eagle-import:10X4")
      (libsource (lib "eagle-import") (part "PAD-10X4"))
    )
    (comp (ref "PAD8")
      (value "PAD-10X4")
      (footprint "eagle-import:10X4")
      (libsource (lib "eagle-import") (part "PAD-10X4"))
    )
    (comp (ref "Q1")
      (value "IRFR2407PBF")
      (footprint "eagle-import:D-PAK")
      (fields
        (field (name "MANF#") "IRFR2407PBF")
        (field (name "PACKAGE") "DPak")
        (field (name "MANF") "International Rectifier")
      )
      (libsource (lib "eagle-import") (part "IRFR2407PBF"))
    )
    (comp (ref "Q2")
      (value "IRFR2407PBF")
      (footprint "eagle-import:D-PAK")
      (fields
        (field (name "MANF#") "IRFR2407PBF")
        (field (name "PACKAGE") "DPak")
        (field (name "MANF") "International Rectifier")
      )
      (libsource (lib "eagle-import") (part "IRFR2407PBF"))
    )
    (comp (ref "Q3")
      (value "IRFR2407PBF")
      (footprint "eagle-import:D-PAK")
      (fields
        (field (name "MANF#") "IRFR2407PBF")
        (field (name "PACKAGE") "DPak")
        (field (name "MANF") "International Rectifier")
      )
      (libsource (lib "eagle-import") (part "IRFR2407PBF"))
    )
    (comp (ref "R18")
      (value "200 µOhms")
      (footprint "eagle-import:R3920-KELVIN")
      (fields
        (field (name "MANF") "Bourns Inc")
        (field (name "POWER") "12W")
        (field (name "TOLERANCE") "±1%")
      )
      (libsource (lib "eagle-import") (part "CURRENT_SHUNT_KELVIN-3920-KELVIN-0.0002R"))
    )
    (comp (ref "R19")
      (value "82K")
      (footprint "eagle-import:R0603")
      (fields
        (field (name "PACKAGE") "0603")
        (field (name "TOLERANCE") "1%")
        (field (name "ALLOCATED") "+")
        (field (name "LCSC#") "C23254")
        (field (name "MANF") "UNI-ROYAL(Uniroyal Elec)")
        (field (name "MANF#") "0603WAF8202T5E")
      )
      (libsource (lib "eagle-import") (part "R-0603-1%"))
    )
    (comp (ref "R20")
      (value "10K2")
      (footprint "eagle-import:R0603")
      (fields
        (field (name "PACKAGE") "0603")
        (field (name "TOLERANCE") "1%")
        (field (name "ALLOCATED") "+")
        (field (name "LCSC#") "C22772")
        (field (name "MANF") "UNI-ROYAL(Uniroyal Elec)")
        (field (name "MANF#") "0603WAF1022T5E")
      )
      (libsource (lib "eagle-import") (part "R-0603-1%"))
    )
    (comp (ref "R21")
      (value "82K")
      (footprint "eagle-import:R0603")
      (fields
        (field (name "PACKAGE") "0603")
        (field (name "TOLERANCE") "1%")
        (field (name "ALLOCATED") "+")
        (field (name "LCSC#") "C23254")
        (field (name "MANF") "UNI-ROYAL(Uniroyal Elec)")
        (field (name "MANF#") "0603WAF8202T5E")
      )
      (libsource (lib "eagle-import") (part "R-0603-1%"))
    )
    (comp (ref "R22")
      (value "82K")
      (footprint "eagle-import:R0603")
      (fields
        (field (name "PACKAGE") "0603")
        (field (name "TOLERANCE") "1%")
        (field (name "ALLOCATED") "+")
        (field (name "LCSC#") "C23254")
        (field (name "MANF") "UNI-ROYAL(Uniroyal Elec)")
        (field (name "MANF#") "0603WAF8202T5E")
      )
      (libsource (lib "eagle-import") (part "R-0603-1%"))
    )
    (comp (ref "R23")
      (value "10K2")
      (footprint "eagle-import:R0603")
      (fields
        (field (name "PACKAGE") "0603")
        (field (name "TOLERANCE") "1%")
        (field (name "ALLOCATED") "+")
        (field (name "LCSC#") "C22772")
        (field (name "MANF") "UNI-ROYAL(Uniroyal Elec)")
        (field (name "MANF#") "0603WAF1022T5E")
      )
      (libsource (lib "eagle-import") (part "R-0603-1%"))
    )
    (comp (ref "R24")
      (value "DNM")
      (footprint "eagle-import:R0603")
      (fields
        (field (name "PACKAGE") "0603")
        (field (name "TOLERANCE") "1%")
        (field (name "ALLOCATED") "+")
        (field (name "LCSC#") "C22772")
        (field (name "MANF") "UNI-ROYAL(Uniroyal Elec)")
        (field (name "MANF#") "0603WAF1022T5E")
      )
      (libsource (lib "eagle-import") (part "R-0603-1%"))
    )
  )
  (nets
    (net (code "1") (name "5V") (class "Default")
      (node (ref "C22") (pin "P$2") (pinfunction "2_P$2") (pintype "passive"))
      (node (ref "C23") (pin "P$2") (pinfunction "2_P$2") (pintype "passive"))
      (node (ref "C24") (pin "P$2") (pinfunction "2_P$2") (pintype "passive"))
      (node (ref "CON4") (pin "1") (pinfunction "1_1") (pintype "passive"))
      (node (ref "CON4") (pin "2") (pinfunction "2_2") (pintype "passive"))
      (node (ref "CON4") (pin "3") (pinfunction "3_3") (pintype "passive"))
      (node (ref "L4") (pin "2") (pinfunction "2_2") (pintype "bidirectional"))
      (node (ref "R11") (pin "2") (pinfunction "2_2") (pintype "passive"))
    )
    (net (code "2") (name "5VFMU") (class "Default")
      (node (ref "C39") (pin "2") (pinfunction "2_2") (pintype "passive"))
      (node (ref "C7") (pin "P$2") (pinfunction "2_P$2") (pintype "passive"))
      (node (ref "C8") (pin "P$2") (pinfunction "2_P$2") (pintype "passive"))
      (node (ref "C9") (pin "P$2") (pinfunction "2_P$2") (pintype "passive"))
      (node (ref "CON1") (pin "10") (pinfunction "10_10") (pintype "passive"))
      (node (ref "CON1") (pin "8") (pinfunction "8_8") (pintype "passive"))
      (node (ref "CON1") (pin "9") (pinfunction "9_9") (pintype "passive"))
      (node (ref "IC5") (pin "5") (pinfunction "V+_5") (pintype "bidirectional"))
      (node (ref "L2") (pin "2") (pinfunction "2_2") (pintype "bidirectional"))
      (node (ref "R3") (pin "2") (pinfunction "2_2") (pintype "passive"))
    )
    (net (code "3") (name "12V") (class "Default")
      (node (ref "C36") (pin "P$2") (pinfunction "2_P$2") (pintype "passive"))
      (node (ref "C37") (pin "P$2") (pinfunction "2_P$2") (pintype "passive"))
      (node (ref "C38") (pin "P$2") (pinfunction "2_P$2") (pintype "passive"))
      (node (ref "CON7") (pin "1") (pinfunction "1_1") (pintype "passive"))
      (node (ref "CON7") (pin "2") (pinfunction "2_2") (pintype "passive"))
      (node (ref "CON7") (pin "3") (pinfunction "3_3") (pintype "passive"))
      (node (ref "L5") (pin "2") (pinfunction "2_2") (pintype "bidirectional"))
      (node (ref "R15") (pin "2") (pinfunction "2_2") (pintype "passive"))
    )
    (net (code "4") (name "24V") (class "Default")
      (node (ref "C28") (pin "2") (pinfunction "2_2") (pintype "passive"))
      (node (ref "C29") (pin "2") (pinfunction "2_2") (pintype "passive"))
      (node (ref "C30") (pin "2") (pinfunction "2_2") (pintype "passive"))
      (node (ref "C31") (pin "2") (pinfunction "2_2") (pintype "passive"))
      (node (ref "C32") (pin "2") (pinfunction "2_2") (pintype "passive"))
      (node (ref "C42") (pin "2") (pinfunction "2_2") (pintype "passive"))
      (node (ref "CON3") (pin "4") (pinfunction "4_4") (pintype "passive"))
      (node (ref "CON3") (pin "5") (pinfunction "5_5") (pintype "passive"))
      (node (ref "CON3") (pin "6") (pinfunction "6_6") (pintype "passive"))
      (node (ref "L3") (pin "2") (pinfunction "2_2") (pintype "bidirectional"))
      (node (ref "R7") (pin "2") (pinfunction "2_2") (pintype "passive"))
    )
    (net (code "5") (name "B1MID") (class "Default")
      (node (ref "B1H") (pin "-") (pinfunction "-_-") (pintype "bidirectional"))
      (node (ref "B1L") (pin "+") (pinfunction "+_+") (pintype "bidirectional"))
      (node (ref "PAD4") (pin "P$1") (pinfunction "P$1_P$1") (pintype "bidirectional"))
      (node (ref "PAD8") (pin "P$1") (pinfunction "P$1_P$1") (pintype "bidirectional"))
    )
    (net (code "6") (name "B2MID") (class "Default")
      (node (ref "B3H") (pin "-") (pinfunction "-_-") (pintype "bidirectional"))
      (node (ref "B3L") (pin "+") (pinfunction "+_+") (pintype "bidirectional"))
      (node (ref "PAD1") (pin "P$1") (pinfunction "P$1_P$1") (pintype "bidirectional"))
      (node (ref "PAD2") (pin "P$1") (pinfunction "P$1_P$1") (pintype "bidirectional"))
    )
    (net (code "7") (name "B3MID") (class "Default")
      (node (ref "B2H") (pin "-") (pinfunction "-_-") (pintype "bidirectional"))
      (node (ref "B2L") (pin "+") (pinfunction "+_+") (pintype "bidirectional"))
      (node (ref "PAD3") (pin "P$1") (pinfunction "P$1_P$1") (pintype "bidirectional"))
      (node (ref "PAD5") (pin "P$1") (pinfunction "P$1_P$1") (pintype "bidirectional"))
    )
    (net (code "8") (name "BATNEG") (class "Default")
      (node (ref "B1L") (pin "-") (pinfunction "-_-") (pintype "bidirectional"))
      (node (ref "B2L") (pin "-") (pinfunction "-_-") (pintype "bidirectional"))
      (node (ref "B3L") (pin "-") (pinfunction "-_-") (pintype "bidirectional"))
      (node (ref "CON3") (pin "7") (pinfunction "7_7") (pintype "passive"))
      (node (ref "D5") (pin "1") (pinfunction "A_1") (pintype "passive"))
      (node (ref "Q1") (pin "S") (pinfunction "S_S") (pintype "passive"))
      (node (ref "Q2") (pin "S") (pinfunction "S_S") (pintype "passive"))
      (node (ref "Q3") (pin "S") (pinfunction "S_S") (pintype "passive"))
      (node (ref "R24") (pin "2") (pinfunction "2_2") (pintype "passive"))
    )
    (net (code "9") (name "BATT_CURRENT") (class "Default")
      (node (ref "C40") (pin "2") (pinfunction "2_2") (pintype "passive"))
      (node (ref "CON1") (pin "12") (pinfunction "12_12") (pintype "passive"))
      (node (ref "IC5") (pin "1") (pinfunction "OUT_1") (pintype "bidirectional"))
      (node (ref "R19") (pin "2") (pinfunction "2_2") (pintype "passive"))
    )
    (net (code "10") (name "BATT_VOLTAGE") (class "Default")
      (node (ref "C41") (pin "2") (pinfunction "2_2") (pintype "passive"))
      (node (ref "CON1") (pin "11") (pinfunction "11_11") (pintype "passive"))
      (node (ref "R20") (pin "2") (pinfunction "2_2") (pintype "passive"))
      (node (ref "R22") (pin "1") (pinfunction "1_1") (pintype "passive"))
    )
    (net (code "11") (name "GND") (class "Default")
      (node (ref "C11") (pin "P$1") (pinfunction "1_P$1") (pintype "passive"))
      (node (ref "C12") (pin "P$1") (pinfunction "1_P$1") (pintype "passive"))
      (node (ref "C13") (pin "P$1") (pinfunction "1_P$1") (pintype "passive"))
      (node (ref "C14") (pin "1") (pinfunction "1_1") (pintype "passive"))
      (node (ref "C15") (pin "1") (pinfunction "1_1") (pintype "passive"))
      (node (ref "C17") (pin "P$1") (pinfunction "1_P$1") (pintype "passive"))
      (node (ref "C18") (pin "P$1") (pinfunction "1_P$1") (pintype "passive"))
      (node (ref "C19") (pin "P$1") (pinfunction "1_P$1") (pintype "passive"))
      (node (ref "C2") (pin "P$1") (pinfunction "1_P$1") (pintype "passive"))
      (node (ref "C20") (pin "1") (pinfunction "1_1") (pintype "passive"))
      (node (ref "C21") (pin "1") (pinfunction "1_1") (pintype "passive"))
      (node (ref "C22") (pin "P$1") (pinfunction "1_P$1") (pintype "passive"))
      (node (ref "C23") (pin "P$1") (pinfunction "1_P$1") (pintype "passive"))
      (node (ref "C24") (pin "P$1") (pinfunction "1_P$1") (pintype "passive"))
      (node (ref "C26") (pin "P$1") (pinfunction "1_P$1") (pintype "passive"))
      (node (ref "C27") (pin "P$1") (pinfunction "1_P$1") (pintype "passive"))
      (node (ref "C28") (pin "1") (pinfunction "1_1") (pintype "passive"))
      (node (ref "C29") (pin "1") (pinfunction "1_1") (pintype "passive"))
      (node (ref "C3") (pin "P$1") (pinfunction "1_P$1") (pintype "passive"))
      (node (ref "C30") (pin "1") (pinfunction "1_1") (pintype "passive"))
      (node (ref "C31") (pin "1") (pinfunction "1_1") (pintype "passive"))
      (node (ref "C32") (pin "1") (pinfunction "1_1") (pintype "passive"))
      (node (ref "C33") (pin "P$1") (pinfunction "1_P$1") (pintype "passive"))
      (node (ref "C34") (pin "1") (pinfunction "1_1") (pintype "passive"))
      (node (ref "C35") (pin "1") (pinfunction "1_1") (pintype "passive"))
      (node (ref "C36") (pin "P$1") (pinfunction "1_P$1") (pintype "passive"))
      (node (ref "C37") (pin "P$1") (pinfunction "1_P$1") (pintype "passive"))
      (node (ref "C38") (pin "P$1") (pinfunction "1_P$1") (pintype "passive"))
      (node (ref "C39") (pin "1") (pinfunction "1_1") (pintype "passive"))
      (node (ref "C4") (pin "P$1") (pinfunction "1_P$1") (pintype "passive"))
      (node (ref "C40") (pin "1") (pinfunction "1_1") (pintype "passive"))
      (node (ref "C41") (pin "1") (pinfunction "1_1") (pintype "passive"))
      (node (ref "C42") (pin "1") (pinfunction "1_1") (pintype "passive"))
      (node (ref "C43") (pin "P$2") (pinfunction "2_P$2") (pintype "passive"))
      (node (ref "C44") (pin "P$1") (pinfunction "1_P$1") (pintype "passive"))
      (node (ref "C5") (pin "1") (pinfunction "1_1") (pintype "passive"))
      (node (ref "C54") (pin "P$1") (pinfunction "1_P$1") (pintype "passive"))
      (node (ref "C56") (pin "P$2") (pinfunction "2_P$2") (pintype "passive"))
      (node (ref "C57") (pin "P$2") (pinfunction "2_P$2") (pintype "passive"))
      (node (ref "C6") (pin "1") (pinfunction "1_1") (pintype "passive"))
      (node (ref "C62") (pin "2") (pinfunction "2_2") (pintype "passive"))
      (node (ref "C7") (pin "P$1") (pinfunction "1_P$1") (pintype "passive"))
      (node (ref "C8") (pin "P$1") (pinfunction "1_P$1") (pintype "passive"))
      (node (ref "C87") (pin "2") (pinfunction "2_2") (pintype "passive"))
      (node (ref "C88") (pin "2") (pinfunction "2_2") (pintype "passive"))
      (node (ref "C9") (pin "P$1") (pinfunction "1_P$1") (pintype "passive"))
      (node (ref "CON1") (pin "1") (pinfunction "1_1") (pintype "passive"))
      (node (ref "CON1") (pin "2") (pinfunction "2_2") (pintype "passive"))
      (node (ref "CON1") (pin "5") (pinfunction "5_5") (pintype "passive"))
      (node (ref "CON1") (pin "6") (pinfunction "6_6") (pintype "passive"))
      (node (ref "CON1") (pin "7") (pinfunction "7_7") (pintype "passive"))
      (node (ref "CON3") (pin "1") (pinfunction "1_1") (pintype "passive"))
      (node (ref "CON3") (pin "2") (pinfunction "2_2") (pintype "passive"))
      (node (ref "CON3") (pin "3") (pinfunction "3_3") (pintype "passive"))
      (node (ref "CON4") (pin "4") (pinfunction "4_4") (pintype "passive"))
      (node (ref "CON4") (pin "5") (pinfunction "5_5") (pintype "passive"))
      (node (ref "CON4") (pin "6") (pinfunction "6_6") (pintype "passive"))
      (node (ref "CON7") (pin "4") (pinfunction "4_4") (pintype "passive"))
      (node (ref "CON7") (pin "5") (pinfunction "5_5") (pintype "passive"))
      (node (ref "CON7") (pin "6") (pinfunction "6_6") (pintype "passive"))
      (node (ref "D1") (pin "A") (pinfunction "A_A") (pintype "passive"))
      (node (ref "D10") (pin "A") (pinfunction "A_A") (pintype "passive"))
      (node (ref "D2") (pin "A") (pinfunction "A_A") (pintype "passive"))
      (node (ref "D3") (pin "A") (pinfunction "A_A") (pintype "passive"))
      (node (ref "D4") (pin "A") (pinfunction "A_A") (pintype "passive"))
      (node (ref "IC1") (pin "7") (pinfunction "GND_7") (pintype "bidirectional"))
      (node (ref "IC1") (pin "P$1") (pinfunction "GND_P$1") (pintype "bidirectional"))
      (node (ref "IC10") (pin "9") (pinfunction "GND_9") (pintype "bidirectional"))
      (node (ref "IC10") (pin "EP") (pinfunction "GND_EP") (pintype "bidirectional"))
      (node (ref "IC2") (pin "7") (pinfunction "GND_7") (pintype "bidirectional"))
      (node (ref "IC2") (pin "P$1") (pinfunction "GND_P$1") (pintype "bidirectional"))
      (node (ref "IC3") (pin "7") (pinfunction "GND_7") (pintype "bidirectional"))
      (node (ref "IC3") (pin "P$1") (pinfunction "GND_P$1") (pintype "bidirectional"))
      (node (ref "IC4") (pin "7") (pinfunction "GND_7") (pintype "bidirectional"))
      (node (ref "IC4") (pin "P$1") (pinfunction "GND_P$1") (pintype "bidirectional"))
      (node (ref "IC5") (pin "2") (pinfunction "GND_2") (pintype "bidirectional"))
      (node (ref "J1") (pin "2") (pinfunction "P$2_2") (pintype "bidirectional"))
      (node (ref "R1") (pin "1") (pinfunction "1_1") (pintype "passive"))
      (node (ref "R12") (pin "1") (pinfunction "1_1") (pintype "passive"))
      (node (ref "R13") (pin "1") (pinfunction "1_1") (pintype "passive"))
      (node (ref "R16") (pin "1") (pinfunction "1_1") (pintype "passive"))
      (node (ref "R17") (pin "1") (pinfunction "1_1") (pintype "passive"))
      (node (ref "R19") (pin "1") (pinfunction "1_1") (pintype "passive"))
      (node (ref "R20") (pin "1") (pinfunction "1_1") (pintype "passive"))
      (node (ref "R25") (pin "1") (pinfunction "1_1") (pintype "passive"))
      (node (ref "R28") (pin "1") (pinfunction "1_1") (pintype "passive"))
      (node (ref "R4") (pin "1") (pinfunction "1_1") (pintype "passive"))
      (node (ref "R5") (pin "1") (pinfunction "1_1") (pintype "passive"))
      (node (ref "R8") (pin "1") (pinfunction "1_1") (pintype "passive"))
      (node (ref "R9") (pin "1") (pinfunction "1_1") (pintype "passive"))
    )
    (net (code "12") (name "Net-(C5-Pad2)") (class "Default")
      (node (ref "C5") (pin "2") (pinfunction "2_2") (pintype "passive"))
      (node (ref "R2") (pin "1") (pinfunction "1_1") (pintype "passive"))
    )
    (net (code "13") (name "Net-(C14-Pad2)") (class "Default")
      (node (ref "C14") (pin "2") (pinfunction "2_2") (pintype "passive"))
      (node (ref "R6") (pin "1") (pinfunction "1_1") (pintype "passive"))
    )
    (net (code "14") (name "Net-(C20-Pad2)") (class "Default")
      (node (ref "C20") (pin "2") (pinfunction "2_2") (pintype "passive"))
      (node (ref "R10") (pin "1") (pinfunction "1_1") (pintype "passive"))
    )
    (net (code "15") (name "Net-(C34-Pad2)") (class "Default")
      (node (ref "C34") (pin "2") (pinfunction "2_2") (pintype "passive"))
      (node (ref "R14") (pin "1") (pinfunction "1_1") (pintype "passive"))
    )
    (net (code "16") (name "Net-(C88-Pad1)") (class "Default")
      (node (ref "C88") (pin "1") (pinfunction "1_1") (pintype "passive"))
      (node (ref "R29") (pin "1") (pinfunction "1_1") (pintype "passive"))
    )
    (net (code "17") (name "Net-(IC1-BOOT)") (class "Default")
      (node (ref "C1") (pin "1") (pinfunction "1_1") (pintype "passive"))
      (node (ref "IC1") (pin "1") (pinfunction "BOOT_1") (pintype "bidirectional"))
    )
    (net (code "18") (name "Net-(IC1-COMP)") (class "Default")
      (node (ref "C6") (pin "2") (pinfunction "2_2") (pintype "passive"))
      (node (ref "IC1") (pin "6") (pinfunction "COMP_6") (pintype "bidirectional"))
      (node (ref "R2") (pin "2") (pinfunction "2_2") (pintype "passive"))
    )
    (net (code "19") (name "Net-(IC1-FB)") (class "Default")
      (node (ref "IC1") (pin "5") (pinfunction "FB_5") (pintype "bidirectional"))
      (node (ref "R3") (pin "1") (pinfunction "1_1") (pintype "passive"))
      (node (ref "R4") (pin "2") (pinfunction "2_2") (pintype "passive"))
    )
    (net (code "20") (name "Net-(IC1-RT{slash}CLK)") (class "Default")
      (node (ref "IC1") (pin "4") (pinfunction "RT/CLK_4") (pintype "bidirectional"))
      (node (ref "R1") (pin "2") (pinfunction "2_2") (pintype "passive"))
    )
    (net (code "21") (name "Net-(IC1-SW)") (class "Default")
      (node (ref "C1") (pin "2") (pinfunction "2_2") (pintype "passive"))
      (node (ref "D1") (pin "C") (pinfunction "C_C") (pintype "passive"))
      (node (ref "IC1") (pin "8") (pinfunction "SW_8") (pintype "bidirectional"))
      (node (ref "L2") (pin "1") (pinfunction "1_1") (pintype "bidirectional"))
    )
    (net (code "22") (name "Net-(IC2-BOOT)") (class "Default")
      (node (ref "C10") (pin "1") (pinfunction "1_1") (pintype "passive"))
      (node (ref "IC2") (pin "1") (pinfunction "BOOT_1") (pintype "bidirectional"))
    )
    (net (code "23") (name "Net-(IC2-COMP)") (class "Default")
      (node (ref "C15") (pin "2") (pinfunction "2_2") (pintype "passive"))
      (node (ref "IC2") (pin "6") (pinfunction "COMP_6") (pintype "bidirectional"))
      (node (ref "R6") (pin "2") (pinfunction "2_2") (pintype "passive"))
    )
    (net (code "24") (name "Net-(IC2-FB)") (class "Default")
      (node (ref "IC2") (pin "5") (pinfunction "FB_5") (pintype "bidirectional"))
      (node (ref "R17") (pin "2") (pinfunction "2_2") (pintype "passive"))
      (node (ref "R7") (pin "1") (pinfunction "1_1") (pintype "passive"))
      (node (ref "R8") (pin "2") (pinfunction "2_2") (pintype "passive"))
    )
    (net (code "25") (name "Net-(IC2-RT{slash}CLK)") (class "Default")
      (node (ref "IC2") (pin "4") (pinfunction "RT/CLK_4") (pintype "bidirectional"))
      (node (ref "R5") (pin "2") (pinfunction "2_2") (pintype "passive"))
    )
    (net (code "26") (name "Net-(IC2-SW)") (class "Default")
      (node (ref "C10") (pin "2") (pinfunction "2_2") (pintype "passive"))
      (node (ref "D2") (pin "C") (pinfunction "C_C") (pintype "passive"))
      (node (ref "IC2") (pin "8") (pinfunction "SW_8") (pintype "bidirectional"))
      (node (ref "L3") (pin "1") (pinfunction "1_1") (pintype "bidirectional"))
    )
    (net (code "27") (name "Net-(IC3-BOOT)") (class "Default")
      (node (ref "C16") (pin "1") (pinfunction "1_1") (pintype "passive"))
      (node (ref "IC3") (pin "1") (pinfunction "BOOT_1") (pintype "bidirectional"))
    )
    (net (code "28") (name "Net-(IC3-COMP)") (class "Default")
      (node (ref "C21") (pin "2") (pinfunction "2_2") (pintype "passive"))
      (node (ref "IC3") (pin "6") (pinfunction "COMP_6") (pintype "bidirectional"))
      (node (ref "R10") (pin "2") (pinfunction "2_2") (pintype "passive"))
    )
    (net (code "29") (name "Net-(IC3-FB)") (class "Default")
      (node (ref "IC3") (pin "5") (pinfunction "FB_5") (pintype "bidirectional"))
      (node (ref "R11") (pin "1") (pinfunction "1_1") (pintype "passive"))
      (node (ref "R12") (pin "2") (pinfunction "2_2") (pintype "passive"))
    )
    (net (code "30") (name "Net-(IC3-RT{slash}CLK)") (class "Default")
      (node (ref "IC3") (pin "4") (pinfunction "RT/CLK_4") (pintype "bidirectional"))
      (node (ref "R9") (pin "2") (pinfunction "2_2") (pintype "passive"))
    )
    (net (code "31") (name "Net-(IC3-SW)") (class "Default")
      (node (ref "C16") (pin "2") (pinfunction "2_2") (pintype "passive"))
      (node (ref "D3") (pin "C") (pinfunction "C_C") (pintype "passive"))
      (node (ref "IC3") (pin "8") (pinfunction "SW_8") (pintype "bidirectional"))
      (node (ref "L4") (pin "1") (pinfunction "1_1") (pintype "bidirectional"))
    )
    (net (code "32") (name "Net-(IC4-BOOT)") (class "Default")
      (node (ref "C25") (pin "1") (pinfunction "1_1") (pintype "passive"))
      (node (ref "IC4") (pin "1") (pinfunction "BOOT_1") (pintype "bidirectional"))
    )
    (net (code "33") (name "Net-(IC4-COMP)") (class "Default")
      (node (ref "C35") (pin "2") (pinfunction "2_2") (pintype "passive"))
      (node (ref "IC4") (pin "6") (pinfunction "COMP_6") (pintype "bidirectional"))
      (node (ref "R14") (pin "2") (pinfunction "2_2") (pintype "passive"))
    )
    (net (code "34") (name "Net-(IC4-FB)") (class "Default")
      (node (ref "IC4") (pin "5") (pinfunction "FB_5") (pintype "bidirectional"))
      (node (ref "R15") (pin "1") (pinfunction "1_1") (pintype "passive"))
      (node (ref "R16") (pin "2") (pinfunction "2_2") (pintype "passive"))
    )
    (net (code "35") (name "Net-(IC4-RT{slash}CLK)") (class "Default")
      (node (ref "IC4") (pin "4") (pinfunction "RT/CLK_4") (pintype "bidirectional"))
      (node (ref "R13") (pin "2") (pinfunction "2_2") (pintype "passive"))
    )
    (net (code "36") (name "Net-(IC4-SW)") (class "Default")
      (node (ref "C25") (pin "2") (pinfunction "2_2") (pintype "passive"))
      (node (ref "D4") (pin "C") (pinfunction "C_C") (pintype "passive"))
      (node (ref "IC4") (pin "8") (pinfunction "SW_8") (pintype "bidirectional"))
      (node (ref "L5") (pin "1") (pinfunction "1_1") (pintype "bidirectional"))
    )
    (net (code "37") (name "Net-(IC5-VIN+)") (class "Default")
      (node (ref "IC5") (pin "3") (pinfunction "VIN+_3") (pintype "bidirectional"))
      (node (ref "R18") (pin "S1") (pinfunction "S1_S1") (pintype "bidirectional"))
    )
    (net (code "38") (name "Net-(IC5-VIN-)") (class "Default")
      (node (ref "IC5") (pin "4") (pinfunction "VIN-_4") (pintype "bidirectional"))
      (node (ref "R18") (pin "S2") (pinfunction "S2_S2") (pintype "bidirectional"))
    )
    (net (code "39") (name "Net-(IC10-BOOT)") (class "Default")
      (node (ref "C58") (pin "2") (pinfunction "2_2") (pintype "passive"))
      (node (ref "IC10") (pin "1") (pinfunction "BOOT_1") (pintype "bidirectional"))
    )
    (net (code "40") (name "Net-(IC10-COMP)") (class "Default")
      (node (ref "C87") (pin "1") (pinfunction "1_1") (pintype "passive"))
      (node (ref "IC10") (pin "8") (pinfunction "COMP_8") (pintype "bidirectional"))
      (node (ref "R29") (pin "2") (pinfunction "2_2") (pintype "passive"))
    )
    (net (code "41") (name "Net-(IC10-PH)") (class "Default")
      (node (ref "C58") (pin "1") (pinfunction "1_1") (pintype "passive"))
      (node (ref "D10") (pin "C") (pinfunction "C_C") (pintype "passive"))
      (node (ref "IC10") (pin "10") (pinfunction "PH_10") (pintype "bidirectional"))
      (node (ref "L1") (pin "P$1") (pinfunction "1_P$1") (pintype "bidirectional"))
    )
    (net (code "42") (name "Net-(IC10-RT{slash}CLK)") (class "Default")
      (node (ref "IC10") (pin "5") (pinfunction "RT/CLK_5") (pintype "bidirectional"))
      (node (ref "R25") (pin "2") (pinfunction "2_2") (pintype "passive"))
    )
    (net (code "43") (name "Net-(IC10-SS{slash}TR)") (class "Default")
      (node (ref "C62") (pin "1") (pinfunction "1_1") (pintype "passive"))
      (node (ref "IC10") (pin "4") (pinfunction "SS/TR_4") (pintype "bidirectional"))
    )
    (net (code "44") (name "Net-(IC10-VSENSE)") (class "Default")
      (node (ref "IC10") (pin "7") (pinfunction "VSENSE_7") (pintype "bidirectional"))
      (node (ref "R27") (pin "1") (pinfunction "1_1") (pintype "passive"))
      (node (ref "R28") (pin "2") (pinfunction "2_2") (pintype "passive"))
    )
    (net (code "45") (name "Net-(R21-Pad1)") (class "Default")
      (node (ref "R21") (pin "1") (pinfunction "1_1") (pintype "passive"))
      (node (ref "R22") (pin "2") (pinfunction "2_2") (pintype "passive"))
    )
    (net (code "46") (name "PGND") (class "Default")
      (node (ref "J1") (pin "1") (pinfunction "P$1_1") (pintype "bidirectional"))
      (node (ref "M1") (pin "-") (pinfunction "-_-") (pintype "bidirectional"))
      (node (ref "M2") (pin "-") (pinfunction "-_-") (pintype "bidirectional"))
      (node (ref "M3") (pin "-") (pinfunction "-_-") (pintype "bidirectional"))
      (node (ref "M4") (pin "-") (pinfunction "-_-") (pintype "bidirectional"))
      (node (ref "M5") (pin "-") (pinfunction "-_-") (pintype "bidirectional"))
      (node (ref "M6") (pin "-") (pinfunction "-_-") (pintype "bidirectional"))
      (node (ref "M7") (pin "-") (pinfunction "-_-") (pintype "bidirectional"))
      (node (ref "Q1") (pin "D") (pinfunction "D_D") (pintype "passive"))
      (node (ref "Q2") (pin "D") (pinfunction "D_D") (pintype "passive"))
      (node (ref "Q3") (pin "D") (pinfunction "D_D") (pintype "passive"))
    )
    (net (code "47") (name "PWRSW") (class "Default")
      (node (ref "CON3") (pin "8") (pinfunction "8_8") (pintype "passive"))
      (node (ref "D5") (pin "3") (pinfunction "C_3") (pintype "passive"))
      (node (ref "Q1") (pin "G") (pinfunction "G_G") (pintype "passive"))
      (node (ref "Q2") (pin "G") (pinfunction "G_G") (pintype "passive"))
      (node (ref "Q3") (pin "G") (pinfunction "G_G") (pintype "passive"))
      (node (ref "R23") (pin "2") (pinfunction "2_2") (pintype "passive"))
      (node (ref "R24") (pin "1") (pinfunction "1_1") (pintype "passive"))
    )
    (net (code "48") (name "VBAT") (class "Default")
      (node (ref "C11") (pin "P$2") (pinfunction "2_P$2") (pintype "passive"))
      (node (ref "C12") (pin "P$2") (pinfunction "2_P$2") (pintype "passive"))
      (node (ref "C13") (pin "P$2") (pinfunction "2_P$2") (pintype "passive"))
      (node (ref "C17") (pin "P$2") (pinfunction "2_P$2") (pintype "passive"))
      (node (ref "C18") (pin "P$2") (pinfunction "2_P$2") (pintype "passive"))
      (node (ref "C19") (pin "P$2") (pinfunction "2_P$2") (pintype "passive"))
      (node (ref "C2") (pin "P$2") (pinfunction "2_P$2") (pintype "passive"))
      (node (ref "C26") (pin "P$2") (pinfunction "2_P$2") (pintype "passive"))
      (node (ref "C27") (pin "P$2") (pinfunction "2_P$2") (pintype "passive"))
      (node (ref "C3") (pin "P$2") (pinfunction "2_P$2") (pintype "passive"))
      (node (ref "C33") (pin "P$2") (pinfunction "2_P$2") (pintype "passive"))
      (node (ref "C4") (pin "P$2") (pinfunction "2_P$2") (pintype "passive"))
      (node (ref "C44") (pin "P$2") (pinfunction "2_P$2") (pintype "passive"))
      (node (ref "C54") (pin "P$2") (pinfunction "2_P$2") (pintype "passive"))
      (node (ref "IC1") (pin "2") (pinfunction "VIN_2") (pintype "bidirectional"))
      (node (ref "IC10") (pin "2") (pinfunction "VIN_2") (pintype "bidirectional"))
      (node (ref "IC2") (pin "2") (pinfunction "VIN_2") (pintype "bidirectional"))
      (node (ref "IC3") (pin "2") (pinfunction "VIN_2") (pintype "bidirectional"))
      (node (ref "IC4") (pin "2") (pinfunction "VIN_2") (pintype "bidirectional"))
      (node (ref "M1") (pin "+") (pinfunction "+_+") (pintype "bidirectional"))
      (node (ref "M2") (pin "+") (pinfunction "+_+") (pintype "bidirectional"))
      (node (ref "M3") (pin "+") (pinfunction "+_+") (pintype "bidirectional"))
      (node (ref "M4") (pin "+") (pinfunction "+_+") (pintype "bidirectional"))
      (node (ref "M5") (pin "+") (pinfunction "+_+") (pintype "bidirectional"))
      (node (ref "M6") (pin "+") (pinfunction "+_+") (pintype "bidirectional"))
      (node (ref "M7") (pin "+") (pinfunction "+_+") (pintype "bidirectional"))
      (node (ref "R18") (pin "2") (pinfunction "2_2") (pintype "bidirectional"))
      (node (ref "R18") (pin "22") (pinfunction "2_22") (pintype "bidirectional"))
      (node (ref "R21") (pin "2") (pinfunction "2_2") (pintype "passive"))
      (node (ref "R23") (pin "1") (pinfunction "1_1") (pintype "passive"))
    )
    (net (code "49") (name "VDC") (class "Default")
      (node (ref "B1H") (pin "+") (pinfunction "+_+") (pintype "bidirectional"))
      (node (ref "B2H") (pin "+") (pinfunction "+_+") (pintype "bidirectional"))
      (node (ref "B3H") (pin "+") (pinfunction "+_+") (pintype "bidirectional"))
      (node (ref "R18") (pin "1") (pinfunction "1_1") (pintype "bidirectional"))
      (node (ref "R18") (pin "11") (pinfunction "1_11") (pintype "bidirectional"))
    )
    (net (code "50") (name "VDD_4V") (class "Default")
      (node (ref "C43") (pin "P$1") (pinfunction "1_P$1") (pintype "passive"))
      (node (ref "C56") (pin "P$1") (pinfunction "1_P$1") (pintype "passive"))
      (node (ref "C57") (pin "P$1") (pinfunction "1_P$1") (pintype "passive"))
      (node (ref "CON1") (pin "3") (pinfunction "3_3") (pintype "passive"))
      (node (ref "CON1") (pin "4") (pinfunction "4_4") (pintype "passive"))
      (node (ref "L1") (pin "P$2") (pinfunction "2_P$2") (pintype "bidirectional"))
      (node (ref "R27") (pin "2") (pinfunction "2_2") (pintype "passive"))
    )
    (net (code "51") (name "unconnected-(B1H-PAD1-PadP$3)") (class "Default")
      (node (ref "B1H") (pin "P$3") (pinfunction "PAD1_P$3") (pintype "bidirectional"))
    )
    (net (code "52") (name "unconnected-(B1H-PAD2-PadP$4)") (class "Default")
      (node (ref "B1H") (pin "P$4") (pinfunction "PAD2_P$4") (pintype "bidirectional"))
    )
    (net (code "53") (name "unconnected-(B1L-PAD1-PadP$3)") (class "Default")
      (node (ref "B1L") (pin "P$3") (pinfunction "PAD1_P$3") (pintype "bidirectional"))
    )
    (net (code "54") (name "unconnected-(B1L-PAD2-PadP$4)") (class "Default")
      (node (ref "B1L") (pin "P$4") (pinfunction "PAD2_P$4") (pintype "bidirectional"))
    )
    (net (code "55") (name "unconnected-(B2H-PAD1-PadP$3)") (class "Default")
      (node (ref "B2H") (pin "P$3") (pinfunction "PAD1_P$3") (pintype "bidirectional"))
    )
    (net (code "56") (name "unconnected-(B2H-PAD2-PadP$4)") (class "Default")
      (node (ref "B2H") (pin "P$4") (pinfunction "PAD2_P$4") (pintype "bidirectional"))
    )
    (net (code "57") (name "unconnected-(B2L-PAD1-PadP$3)") (class "Default")
      (node (ref "B2L") (pin "P$3") (pinfunction "PAD1_P$3") (pintype "bidirectional"))
    )
    (net (code "58") (name "unconnected-(B2L-PAD2-PadP$4)") (class "Default")
      (node (ref "B2L") (pin "P$4") (pinfunction "PAD2_P$4") (pintype "bidirectional"))
    )
    (net (code "59") (name "unconnected-(B3H-PAD1-PadP$3)") (class "Default")
      (node (ref "B3H") (pin "P$3") (pinfunction "PAD1_P$3") (pintype "bidirectional"))
    )
    (net (code "60") (name "unconnected-(B3H-PAD2-PadP$4)") (class "Default")
      (node (ref "B3H") (pin "P$4") (pinfunction "PAD2_P$4") (pintype "bidirectional"))
    )
    (net (code "61") (name "unconnected-(B3L-PAD1-PadP$3)") (class "Default")
      (node (ref "B3L") (pin "P$3") (pinfunction "PAD1_P$3") (pintype "bidirectional"))
    )
    (net (code "62") (name "unconnected-(B3L-PAD2-PadP$4)") (class "Default")
      (node (ref "B3L") (pin "P$4") (pinfunction "PAD2_P$4") (pintype "bidirectional"))
    )
    (net (code "63") (name "unconnected-(IC1-EN-Pad3)") (class "Default")
      (node (ref "IC1") (pin "3") (pinfunction "EN_3") (pintype "bidirectional"))
    )
    (net (code "64") (name "unconnected-(IC2-EN-Pad3)") (class "Default")
      (node (ref "IC2") (pin "3") (pinfunction "EN_3") (pintype "bidirectional"))
    )
    (net (code "65") (name "unconnected-(IC3-EN-Pad3)") (class "Default")
      (node (ref "IC3") (pin "3") (pinfunction "EN_3") (pintype "bidirectional"))
    )
    (net (code "66") (name "unconnected-(IC4-EN-Pad3)") (class "Default")
      (node (ref "IC4") (pin "3") (pinfunction "EN_3") (pintype "bidirectional"))
    )
    (net (code "67") (name "unconnected-(IC10-EN-Pad3)") (class "Default")
      (node (ref "IC10") (pin "3") (pinfunction "EN_3") (pintype "bidirectional"))
    )
    (net (code "68") (name "unconnected-(IC10-PWRGD-Pad6)") (class "Default")
      (node (ref "IC10") (pin "6") (pinfunction "PWRGD_6") (pintype "bidirectional"))
    )
    (net (code "69") (name "unconnected-(M1-PAD1-PadP$3)") (class "Default")
      (node (ref "M1") (pin "P$3") (pinfunction "PAD1_P$3") (pintype "bidirectional"))
    )
    (net (code "70") (name "unconnected-(M1-PAD2-PadP$4)") (class "Default")
      (node (ref "M1") (pin "P$4") (pinfunction "PAD2_P$4") (pintype "bidirectional"))
    )
    (net (code "71") (name "unconnected-(M2-PAD1-PadP$3)") (class "Default")
      (node (ref "M2") (pin "P$3") (pinfunction "PAD1_P$3") (pintype "bidirectional"))
    )
    (net (code "72") (name "unconnected-(M2-PAD2-PadP$4)") (class "Default")
      (node (ref "M2") (pin "P$4") (pinfunction "PAD2_P$4") (pintype "bidirectional"))
    )
    (net (code "73") (name "unconnected-(M3-PAD1-PadP$3)") (class "Default")
      (node (ref "M3") (pin "P$3") (pinfunction "PAD1_P$3") (pintype "bidirectional"))
    )
    (net (code "74") (name "unconnected-(M3-PAD2-PadP$4)") (class "Default")
      (node (ref "M3") (pin "P$4") (pinfunction "PAD2_P$4") (pintype "bidirectional"))
    )
    (net (code "75") (name "unconnected-(M4-PAD1-PadP$3)") (class "Default")
      (node (ref "M4") (pin "P$3") (pinfunction "PAD1_P$3") (pintype "bidirectional"))
    )
    (net (code "76") (name "unconnected-(M4-PAD2-PadP$4)") (class "Default")
      (node (ref "M4") (pin "P$4") (pinfunction "PAD2_P$4") (pintype "bidirectional"))
    )
    (net (code "77") (name "unconnected-(M5-PAD1-PadP$3)") (class "Default")
      (node (ref "M5") (pin "P$3") (pinfunction "PAD1_P$3") (pintype "bidirectional"))
    )
    (net (code "78") (name "unconnected-(M5-PAD2-PadP$4)") (class "Default")
      (node (ref "M5") (pin "P$4") (pinfunction "PAD2_P$4") (pintype "bidirectional"))
    )
    (net (code "79") (name "unconnected-(M6-PAD1-PadP$3)") (class "Default")
      (node (ref "M6") (pin "P$3") (pinfunction "PAD1_P$3") (pintype "bidirectional"))
    )
    (net (code "80") (name "unconnected-(M6-PAD2-PadP$4)") (class "Default")
      (node (ref "M6") (pin "P$4") (pinfunction "PAD2_P$4") (pintype "bidirectional"))
    )
    (net (code "81") (name "unconnected-(M7-PAD1-PadP$3)") (class "Default")
      (node (ref "M7") (pin "P$3") (pinfunction "PAD1_P$3") (pintype "bidirectional"))
    )
    (net (code "82") (name "unconnected-(M7-PAD2-PadP$4)") (class "Default")
      (node (ref "M7") (pin "P$4") (pinfunction "PAD2_P$4") (pintype "bidirectional"))
    )
  )
)
